# Edith.net
KiCad netlist of a schematic drawn in EAGLE
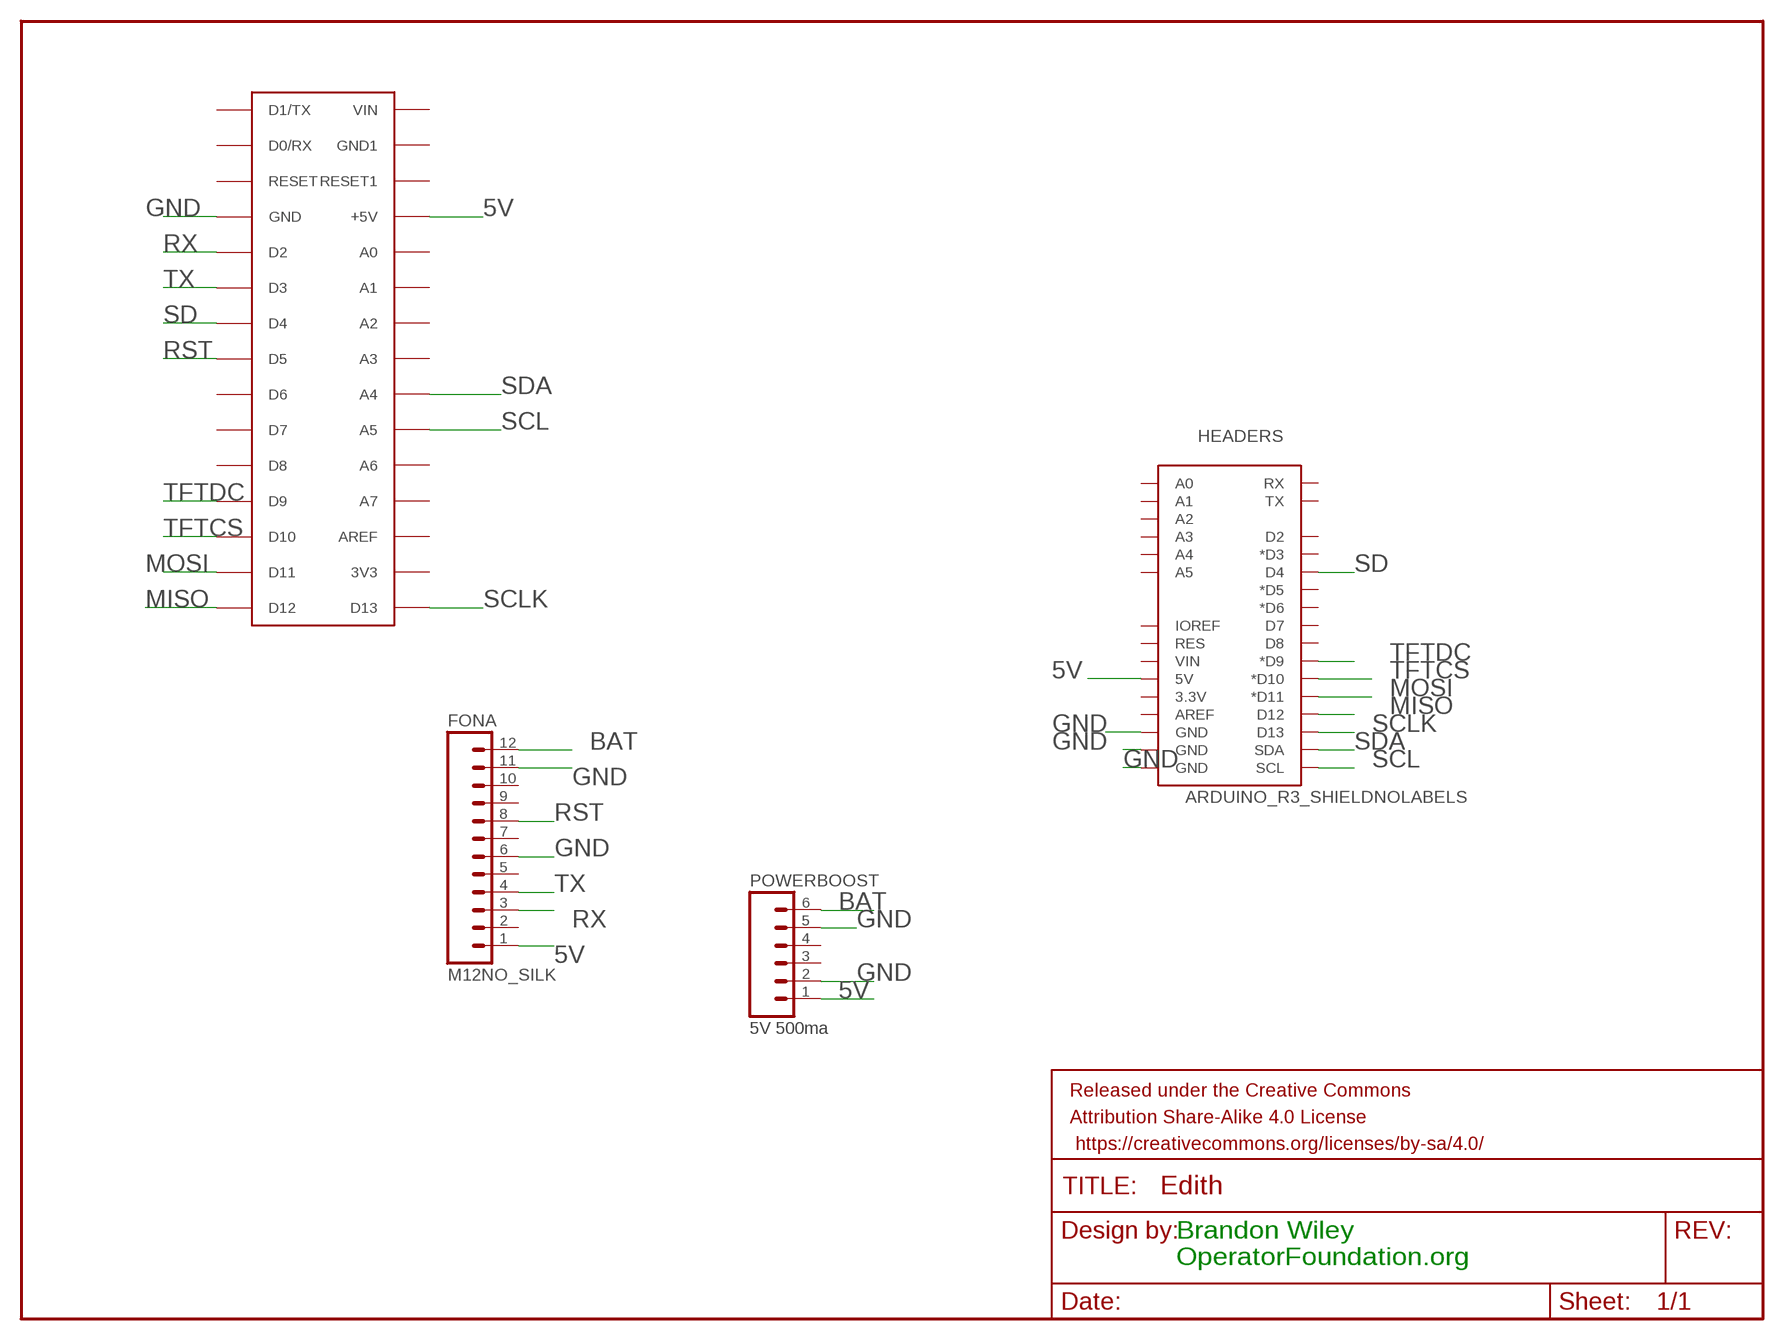
[diagram p0: schematic, sheet 1]

(export (version "E")
  (design (tool "Eeschema 10.0.6"))
  (components
    (comp (ref "FONA")
      (value "M12NO_SILK")
      (footprint "eagle-import:1X12_NO_SILK")
      (libsource (lib "eagle-import") (part "M12NO_SILK"))
    )
    (comp (ref "FRAME1")
      (value "FRAME-LETTER")
      (footprint "eagle-import:CREATIVE_COMMONS")
      (libsource (lib "eagle-import") (part "FRAME-LETTER"))
    )
    (comp (ref "HEADERS")
      (value "ARDUINO_R3_SHIELDNOLABELS")
      (footprint "eagle-import:UNO_R3_SHIELD_NOLABELS")
      (libsource (lib "eagle-import") (part "ARDUINO_R3_SHIELDNOLABELS"))
    )
    (comp (ref "POWERBOOST")
      (value "5V 500ma")
      (footprint "eagle-import:1X06_NO_SILK")
      (libsource (lib "eagle-import") (part "M06NO_SILK"))
    )
    (comp (ref "U$1")
      (value "ARDUINONANO")
      (footprint "eagle-import:PDIP-32")
      (libsource (lib "eagle-import") (part "ARDUINONANO"))
    )
  )
  (nets
    (net (code "1") (name "/5V") (class "Default")
      (node (ref "FONA") (pin "1") (pinfunction "1_1") (pintype "passive"))
      (node (ref "HEADERS") (pin "5V") (pinfunction "5V_5V") (pintype "bidirectional"))
      (node (ref "POWERBOOST") (pin "1") (pinfunction "1_1") (pintype "passive"))
      (node (ref "U$1") (pin "+5V") (pinfunction "+5V_+5V") (pintype "bidirectional"))
    )
    (net (code "2") (name "/BAT") (class "Default")
      (node (ref "FONA") (pin "12") (pinfunction "12_12") (pintype "passive"))
      (node (ref "POWERBOOST") (pin "6") (pinfunction "6_6") (pintype "passive"))
    )
    (net (code "3") (name "/GND") (class "Default")
      (node (ref "FONA") (pin "11") (pinfunction "11_11") (pintype "passive"))
      (node (ref "FONA") (pin "6") (pinfunction "6_6") (pintype "passive"))
      (node (ref "HEADERS") (pin "GND@0") (pinfunction "GND_GND@0") (pintype "bidirectional"))
      (node (ref "HEADERS") (pin "GND@1") (pinfunction "GND_GND@1") (pintype "bidirectional"))
      (node (ref "HEADERS") (pin "GND@2") (pinfunction "GND_GND@2") (pintype "bidirectional"))
      (node (ref "POWERBOOST") (pin "2") (pinfunction "2_2") (pintype "passive"))
      (node (ref "POWERBOOST") (pin "5") (pinfunction "5_5") (pintype "passive"))
      (node (ref "U$1") (pin "GND") (pinfunction "GND_GND") (pintype "bidirectional"))
    )
    (net (code "4") (name "/MISO") (class "Default")
      (node (ref "HEADERS") (pin "D12") (pinfunction "D12_D12") (pintype "bidirectional"))
      (node (ref "U$1") (pin "D12") (pinfunction "D12_D12") (pintype "bidirectional"))
    )
    (net (code "5") (name "/MOSI") (class "Default")
      (node (ref "HEADERS") (pin "D11") (pinfunction "*D11_D11") (pintype "bidirectional"))
      (node (ref "U$1") (pin "D11") (pinfunction "D11_D11") (pintype "bidirectional"))
    )
    (net (code "6") (name "/RST") (class "Default")
      (node (ref "FONA") (pin "8") (pinfunction "8_8") (pintype "passive"))
      (node (ref "U$1") (pin "D5") (pinfunction "D5_D5") (pintype "bidirectional"))
    )
    (net (code "7") (name "/RX") (class "Default")
      (node (ref "FONA") (pin "3") (pinfunction "3_3") (pintype "passive"))
      (node (ref "U$1") (pin "D2") (pinfunction "D2_D2") (pintype "bidirectional"))
    )
    (net (code "8") (name "/SCL") (class "Default")
      (node (ref "HEADERS") (pin "SCL") (pinfunction "SCL_SCL") (pintype "bidirectional"))
      (node (ref "U$1") (pin "A5") (pinfunction "A5_A5") (pintype "bidirectional"))
    )
    (net (code "9") (name "/SCLK") (class "Default")
      (node (ref "HEADERS") (pin "D13") (pinfunction "D13_D13") (pintype "bidirectional"))
      (node (ref "U$1") (pin "D13") (pinfunction "D13_D13") (pintype "bidirectional"))
    )
    (net (code "10") (name "/SD") (class "Default")
      (node (ref "HEADERS") (pin "D4") (pinfunction "D4_D4") (pintype "bidirectional"))
      (node (ref "U$1") (pin "D4") (pinfunction "D4_D4") (pintype "bidirectional"))
    )
    (net (code "11") (name "/SDA") (class "Default")
      (node (ref "HEADERS") (pin "SDA") (pinfunction "SDA_SDA") (pintype "bidirectional"))
      (node (ref "U$1") (pin "A4") (pinfunction "A4_A4") (pintype "bidirectional"))
    )
    (net (code "12") (name "/TFTCS") (class "Default")
      (node (ref "HEADERS") (pin "D10") (pinfunction "*D10_D10") (pintype "bidirectional"))
      (node (ref "U$1") (pin "D10") (pinfunction "D10_D10") (pintype "bidirectional"))
    )
    (net (code "13") (name "/TFTDC") (class "Default")
      (node (ref "HEADERS") (pin "D9") (pinfunction "*D9_D9") (pintype "bidirectional"))
      (node (ref "U$1") (pin "D9") (pinfunction "D9_D9") (pintype "bidirectional"))
    )
    (net (code "14") (name "/TX") (class "Default")
      (node (ref "FONA") (pin "4") (pinfunction "4_4") (pintype "passive"))
      (node (ref "U$1") (pin "D3") (pinfunction "D3_D3") (pintype "bidirectional"))
    )
    (net (code "15") (name "unconnected-(FONA-Pad2)") (class "Default")
      (node (ref "FONA") (pin "2") (pinfunction "2_2") (pintype "passive"))
    )
    (net (code "16") (name "unconnected-(FONA-Pad5)") (class "Default")
      (node (ref "FONA") (pin "5") (pinfunction "5_5") (pintype "passive"))
    )
    (net (code "17") (name "unconnected-(FONA-Pad7)") (class "Default")
      (node (ref "FONA") (pin "7") (pinfunction "7_7") (pintype "passive"))
    )
    (net (code "18") (name "unconnected-(FONA-Pad9)") (class "Default")
      (node (ref "FONA") (pin "9") (pinfunction "9_9") (pintype "passive"))
    )
    (net (code "19") (name "unconnected-(FONA-Pad10)") (class "Default")
      (node (ref "FONA") (pin "10") (pinfunction "10_10") (pintype "passive"))
    )
    (net (code "20") (name "unconnected-(HEADERS-*D3-PadD3)") (class "Default")
      (node (ref "HEADERS") (pin "D3") (pinfunction "*D3_D3") (pintype "bidirectional"))
    )
    (net (code "21") (name "unconnected-(HEADERS-*D5-PadD5)") (class "Default")
      (node (ref "HEADERS") (pin "D5") (pinfunction "*D5_D5") (pintype "bidirectional"))
    )
    (net (code "22") (name "unconnected-(HEADERS-*D6-PadD6)") (class "Default")
      (node (ref "HEADERS") (pin "D6") (pinfunction "*D6_D6") (pintype "bidirectional"))
    )
    (net (code "23") (name "unconnected-(HEADERS-Pad3.3V)") (class "Default")
      (node (ref "HEADERS") (pin "3.3V") (pinfunction "3.3V_3.3V") (pintype "bidirectional"))
    )
    (net (code "24") (name "unconnected-(HEADERS-PadA0)") (class "Default")
      (node (ref "HEADERS") (pin "A0") (pinfunction "A0_A0") (pintype "bidirectional"))
    )
    (net (code "25") (name "unconnected-(HEADERS-PadA1)") (class "Default")
      (node (ref "HEADERS") (pin "A1") (pinfunction "A1_A1") (pintype "bidirectional"))
    )
    (net (code "26") (name "unconnected-(HEADERS-PadA2)") (class "Default")
      (node (ref "HEADERS") (pin "A2") (pinfunction "A2_A2") (pintype "bidirectional"))
    )
    (net (code "27") (name "unconnected-(HEADERS-PadA3)") (class "Default")
      (node (ref "HEADERS") (pin "A3") (pinfunction "A3_A3") (pintype "bidirectional"))
    )
    (net (code "28") (name "unconnected-(HEADERS-PadA4)") (class "Default")
      (node (ref "HEADERS") (pin "A4") (pinfunction "A4_A4") (pintype "bidirectional"))
    )
    (net (code "29") (name "unconnected-(HEADERS-PadA5)") (class "Default")
      (node (ref "HEADERS") (pin "A5") (pinfunction "A5_A5") (pintype "bidirectional"))
    )
    (net (code "30") (name "unconnected-(HEADERS-PadAREF)") (class "Default")
      (node (ref "HEADERS") (pin "AREF") (pinfunction "AREF_AREF") (pintype "bidirectional"))
    )
    (net (code "31") (name "unconnected-(HEADERS-PadD2)") (class "Default")
      (node (ref "HEADERS") (pin "D2") (pinfunction "D2_D2") (pintype "bidirectional"))
    )
    (net (code "32") (name "unconnected-(HEADERS-PadD7)") (class "Default")
      (node (ref "HEADERS") (pin "D7") (pinfunction "D7_D7") (pintype "bidirectional"))
    )
    (net (code "33") (name "unconnected-(HEADERS-PadD8)") (class "Default")
      (node (ref "HEADERS") (pin "D8") (pinfunction "D8_D8") (pintype "bidirectional"))
    )
    (net (code "34") (name "unconnected-(HEADERS-PadIOREF)") (class "Default")
      (node (ref "HEADERS") (pin "IOREF") (pinfunction "IOREF_IOREF") (pintype "bidirectional"))
    )
    (net (code "35") (name "unconnected-(HEADERS-PadRES)") (class "Default")
      (node (ref "HEADERS") (pin "RES") (pinfunction "RES_RES") (pintype "bidirectional"))
    )
    (net (code "36") (name "unconnected-(HEADERS-PadRX)") (class "Default")
      (node (ref "HEADERS") (pin "RX") (pinfunction "RX_RX") (pintype "bidirectional"))
    )
    (net (code "37") (name "unconnected-(HEADERS-PadTX)") (class "Default")
      (node (ref "HEADERS") (pin "TX") (pinfunction "TX_TX") (pintype "bidirectional"))
    )
    (net (code "38") (name "unconnected-(HEADERS-PadVIN)") (class "Default")
      (node (ref "HEADERS") (pin "VIN") (pinfunction "VIN_VIN") (pintype "bidirectional"))
    )
    (net (code "39") (name "unconnected-(POWERBOOST-Pad3)") (class "Default")
      (node (ref "POWERBOOST") (pin "3") (pinfunction "3_3") (pintype "passive"))
    )
    (net (code "40") (name "unconnected-(POWERBOOST-Pad4)") (class "Default")
      (node (ref "POWERBOOST") (pin "4") (pinfunction "4_4") (pintype "passive"))
    )
    (net (code "41") (name "unconnected-(U$1-Pad3V3)") (class "Default")
      (node (ref "U$1") (pin "3V3") (pinfunction "3V3_3V3") (pintype "bidirectional"))
    )
    (net (code "42") (name "unconnected-(U$1-PadA0)") (class "Default")
      (node (ref "U$1") (pin "A0") (pinfunction "A0_A0") (pintype "bidirectional"))
    )
    (net (code "43") (name "unconnected-(U$1-PadA1)") (class "Default")
      (node (ref "U$1") (pin "A1") (pinfunction "A1_A1") (pintype "bidirectional"))
    )
    (net (code "44") (name "unconnected-(U$1-PadA2)") (class "Default")
      (node (ref "U$1") (pin "A2") (pinfunction "A2_A2") (pintype "bidirectional"))
    )
    (net (code "45") (name "unconnected-(U$1-PadA3)") (class "Default")
      (node (ref "U$1") (pin "A3") (pinfunction "A3_A3") (pintype "bidirectional"))
    )
    (net (code "46") (name "unconnected-(U$1-PadA6)") (class "Default")
      (node (ref "U$1") (pin "A6") (pinfunction "A6_A6") (pintype "bidirectional"))
    )
    (net (code "47") (name "unconnected-(U$1-PadA7)") (class "Default")
      (node (ref "U$1") (pin "A7") (pinfunction "A7_A7") (pintype "bidirectional"))
    )
    (net (code "48") (name "unconnected-(U$1-PadAREF)") (class "Default")
      (node (ref "U$1") (pin "AREF") (pinfunction "AREF_AREF") (pintype "bidirectional"))
    )
    (net (code "49") (name "unconnected-(U$1-PadD0{slash}RX)") (class "Default")
      (node (ref "U$1") (pin "D0/RX") (pinfunction "D0/RX_D0/RX") (pintype "bidirectional"))
    )
    (net (code "50") (name "unconnected-(U$1-PadD1{slash}TX)") (class "Default")
      (node (ref "U$1") (pin "D1/TX") (pinfunction "D1/TX_D1/TX") (pintype "bidirectional"))
    )
    (net (code "51") (name "unconnected-(U$1-PadD6)") (class "Default")
      (node (ref "U$1") (pin "D6") (pinfunction "D6_D6") (pintype "bidirectional"))
    )
    (net (code "52") (name "unconnected-(U$1-PadD7)") (class "Default")
      (node (ref "U$1") (pin "D7") (pinfunction "D7_D7") (pintype "bidirectional"))
    )
    (net (code "53") (name "unconnected-(U$1-PadD8)") (class "Default")
      (node (ref "U$1") (pin "D8") (pinfunction "D8_D8") (pintype "bidirectional"))
    )
    (net (code "54") (name "unconnected-(U$1-PadGND1)") (class "Default")
      (node (ref "U$1") (pin "GND1") (pinfunction "GND1_GND1") (pintype "bidirectional"))
    )
    (net (code "55") (name "unconnected-(U$1-PadRESET)") (class "Default")
      (node (ref "U$1") (pin "RESET") (pinfunction "RESET_RESET") (pintype "bidirectional"))
    )
    (net (code "56") (name "unconnected-(U$1-PadRESET1)") (class "Default")
      (node (ref "U$1") (pin "RESET1") (pinfunction "RESET1_RESET1") (pintype "bidirectional"))
    )
    (net (code "57") (name "unconnected-(U$1-PadVIN)") (class "Default")
      (node (ref "U$1") (pin "VIN") (pinfunction "VIN_VIN") (pintype "bidirectional"))
    )
  )
)
